# RS232_485_SDcard.net
KiCad netlist of a schematic drawn in Altium Designer
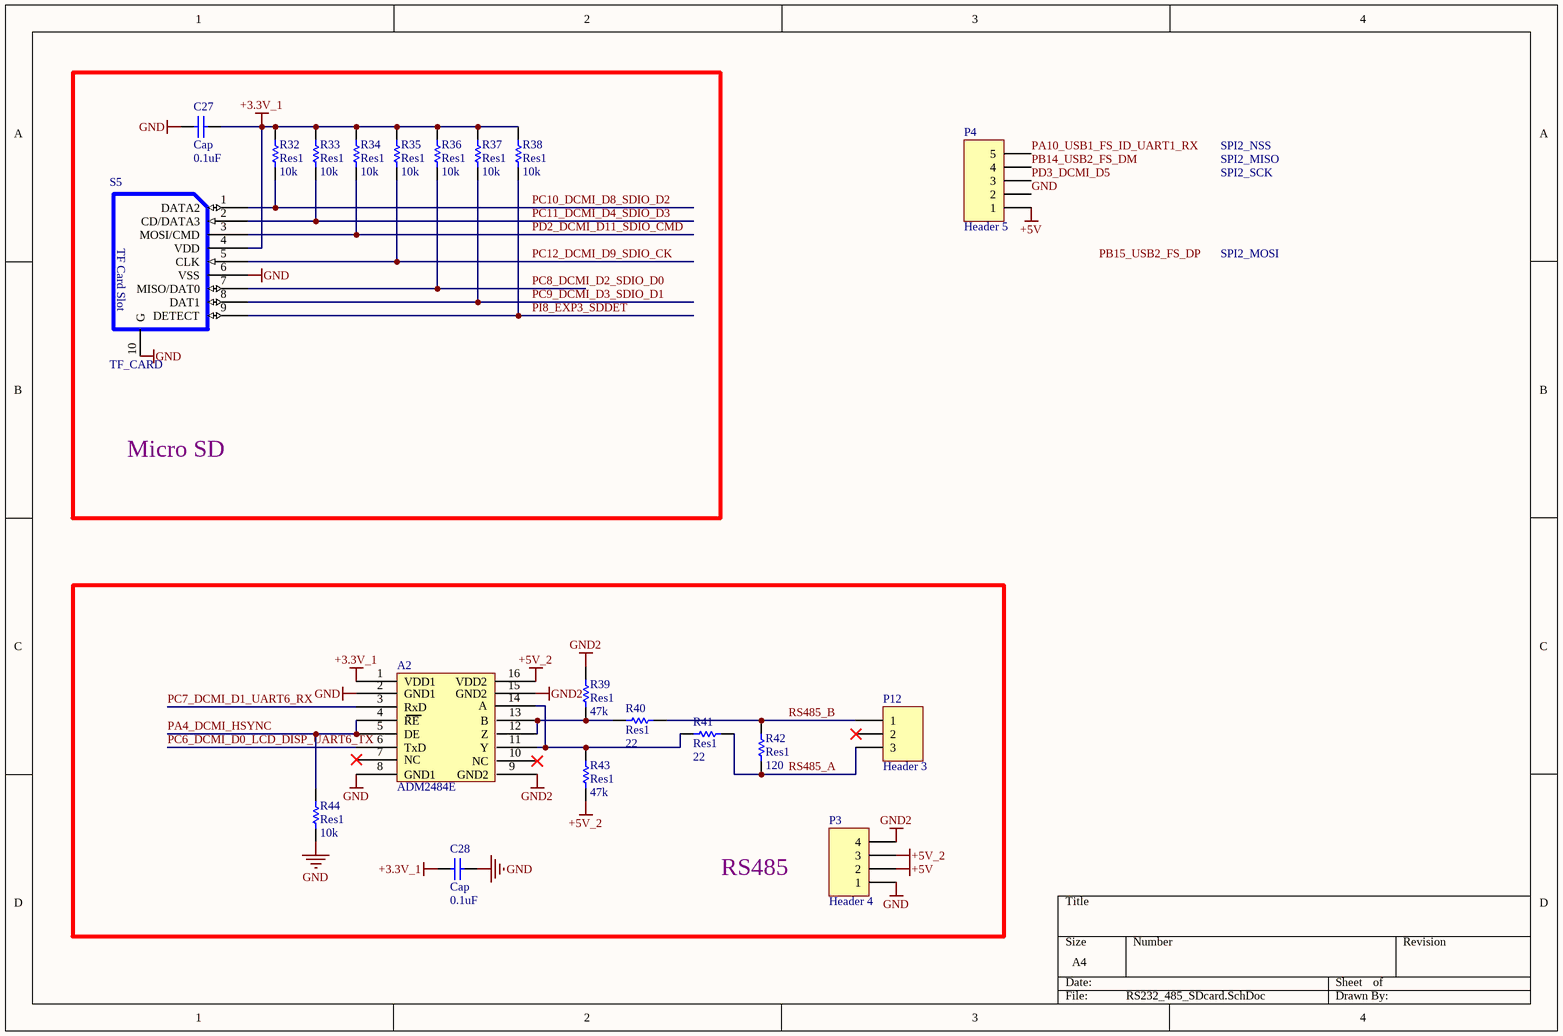
[diagram p0: RS232_485_SDcard.SchDoc]

(export (version "E")
  (design (tool "Eeschema 10.0.6"))
  (components
    (comp (ref "A2") (value "ADM2484E") (footprint "RW-16") (libsource (lib "lib-KJ") (part "ADM2484E")))
    (comp (ref "C27")
      (value "Cap")
      (footprint "0805_C")
      (description "Capacitor")
      (fields (field (name "ALTIUM_VALUE") "0.1uF") (field (name "PUBLISHER") "Altium Limited"))
      (libsource (lib "Miscellaneous Devices") (part "Cap"))
    )
    (comp (ref "C28")
      (value "Cap")
      (footprint "0805_C")
      (description "Capacitor")
      (fields (field (name "ALTIUM_VALUE") "0.1uF") (field (name "PUBLISHER") "Altium Limited"))
      (libsource (lib "Miscellaneous Devices") (part "Cap"))
    )
    (comp (ref "P3")
      (value "Header 4")
      (footprint "B0505S-1W")
      (description "Header, 4-Pin")
      (fields (field (name "PUBLISHER") "Altium Limited"))
      (libsource (lib "Miscellaneous Connectors") (part "Header 4"))
    )
    (comp (ref "P4")
      (value "Header 5")
      (footprint "DIN 固定座 方型 5P TO PCB 2003")
      (description "Header, 5-Pin")
      (fields (field (name "PUBLISHER") "Altium Limited"))
      (libsource (lib "Miscellaneous Connectors") (part "Header 5"))
    )
    (comp (ref "P12")
      (value "Header 3")
      (footprint "歐式端子*3p")
      (description "Header, 3-Pin")
      (fields (field (name "PUBLISHER") "Altium Limited"))
      (libsource (lib "Miscellaneous Connectors") (part "Header 3"))
    )
    (comp (ref "R32")
      (value "Res1")
      (footprint "0805_C")
      (description "Resistor")
      (fields (field (name "ALTIUM_VALUE") "10k") (field (name "PUBLISHER") "Altium Limited"))
      (libsource (lib "Miscellaneous Devices") (part "Res1"))
    )
    (comp (ref "R33")
      (value "Res1")
      (footprint "0805_C")
      (description "Resistor")
      (fields (field (name "ALTIUM_VALUE") "10k") (field (name "PUBLISHER") "Altium Limited"))
      (libsource (lib "Miscellaneous Devices") (part "Res1"))
    )
    (comp (ref "R34")
      (value "Res1")
      (footprint "0805_C")
      (description "Resistor")
      (fields (field (name "ALTIUM_VALUE") "10k") (field (name "PUBLISHER") "Altium Limited"))
      (libsource (lib "Miscellaneous Devices") (part "Res1"))
    )
    (comp (ref "R35")
      (value "Res1")
      (footprint "0805_C")
      (description "Resistor")
      (fields (field (name "ALTIUM_VALUE") "10k") (field (name "PUBLISHER") "Altium Limited"))
      (libsource (lib "Miscellaneous Devices") (part "Res1"))
    )
    (comp (ref "R36")
      (value "Res1")
      (footprint "0805_C")
      (description "Resistor")
      (fields (field (name "ALTIUM_VALUE") "10k") (field (name "PUBLISHER") "Altium Limited"))
      (libsource (lib "Miscellaneous Devices") (part "Res1"))
    )
    (comp (ref "R37")
      (value "Res1")
      (footprint "0805_C")
      (description "Resistor")
      (fields (field (name "ALTIUM_VALUE") "10k") (field (name "PUBLISHER") "Altium Limited"))
      (libsource (lib "Miscellaneous Devices") (part "Res1"))
    )
    (comp (ref "R38")
      (value "Res1")
      (footprint "0805_C")
      (description "Resistor")
      (fields (field (name "ALTIUM_VALUE") "10k") (field (name "PUBLISHER") "Altium Limited"))
      (libsource (lib "Miscellaneous Devices") (part "Res1"))
    )
    (comp (ref "R39")
      (value "Res1")
      (footprint "0805_C")
      (description "Resistor")
      (fields (field (name "ALTIUM_VALUE") "47k") (field (name "PUBLISHER") "Altium Limited"))
      (libsource (lib "Miscellaneous Devices") (part "Res1"))
    )
    (comp (ref "R40")
      (value "Res1")
      (footprint "0805_C")
      (description "Resistor")
      (fields (field (name "ALTIUM_VALUE") "22") (field (name "PUBLISHER") "Altium Limited"))
      (libsource (lib "Miscellaneous Devices") (part "Res1"))
    )
    (comp (ref "R41")
      (value "Res1")
      (footprint "0805_C")
      (description "Resistor")
      (fields (field (name "ALTIUM_VALUE") "22") (field (name "PUBLISHER") "Altium Limited"))
      (libsource (lib "Miscellaneous Devices") (part "Res1"))
    )
    (comp (ref "R42")
      (value "Res1")
      (footprint "0805_C")
      (description "Resistor")
      (fields (field (name "ALTIUM_VALUE") "120") (field (name "PUBLISHER") "Altium Limited"))
      (libsource (lib "Miscellaneous Devices") (part "Res1"))
    )
    (comp (ref "R43")
      (value "Res1")
      (footprint "0805_C")
      (description "Resistor")
      (fields (field (name "ALTIUM_VALUE") "47k") (field (name "PUBLISHER") "Altium Limited"))
      (libsource (lib "Miscellaneous Devices") (part "Res1"))
    )
    (comp (ref "R44")
      (value "Res1")
      (footprint "0805_C")
      (description "Resistor")
      (fields (field (name "ALTIUM_VALUE") "10k") (field (name "PUBLISHER") "Altium Limited"))
      (libsource (lib "Miscellaneous Devices") (part "Res1"))
    )
    (comp (ref "S5")
      (value "TF_CARD")
      (footprint "TF-CARD")
      (libsource (lib "STM32F4x9IG-Mother-B-SCH") (part "TF_CARD"))
    )
  )
  (nets
    (net (code "1") (name "+3.3V_1") (class "Default")
      (node (ref "A2") (pin "1") (pinfunction "VDD1_1") (pintype "passive"))
      (node (ref "C27") (pin "1") (pinfunction "1_1") (pintype "passive"))
      (node (ref "C28") (pin "1") (pinfunction "1_1") (pintype "passive"))
      (node (ref "R32") (pin "1") (pinfunction "1_1") (pintype "passive"))
      (node (ref "R33") (pin "1") (pinfunction "1_1") (pintype "passive"))
      (node (ref "R34") (pin "1") (pinfunction "1_1") (pintype "passive"))
      (node (ref "R35") (pin "1") (pinfunction "1_1") (pintype "passive"))
      (node (ref "R36") (pin "1") (pinfunction "1_1") (pintype "passive"))
      (node (ref "R37") (pin "1") (pinfunction "1_1") (pintype "passive"))
      (node (ref "R38") (pin "1") (pinfunction "1_1") (pintype "passive"))
      (node (ref "S5") (pin "4") (pinfunction "VDD_4") (pintype "power_in"))
    )
    (net (code "2") (name "+5V") (class "Default")
      (node (ref "P3") (pin "2") (pinfunction "2_2") (pintype "passive"))
      (node (ref "P4") (pin "1") (pinfunction "1_1") (pintype "passive"))
    )
    (net (code "3") (name "+5V_2") (class "Default")
      (node (ref "A2") (pin "16") (pinfunction "VDD2_16") (pintype "passive"))
      (node (ref "P3") (pin "3") (pinfunction "3_3") (pintype "passive"))
      (node (ref "R43") (pin "2") (pinfunction "2_2") (pintype "passive"))
    )
    (net (code "4") (name "/PA4_DCMI_HSYNC") (class "Default")
      (node (ref "A2") (pin "4") (pinfunction "RE_4") (pintype "passive"))
      (node (ref "A2") (pin "5") (pinfunction "DE_5") (pintype "passive"))
      (node (ref "R44") (pin "2") (pinfunction "2_2") (pintype "passive"))
    )
    (net (code "5") (name "/PA10_USB1_FS_ID_UART1_RX") (class "Default")
      (node (ref "P4") (pin "5") (pinfunction "5_5") (pintype "passive"))
    )
    (net (code "6") (name "/PB14_USB2_FS_DM") (class "Default")
      (node (ref "P4") (pin "4") (pinfunction "4_4") (pintype "passive"))
    )
    (net (code "8") (name "/PC6_DCMI_D0_LCD_DISP_UART6_TX") (class "Default")
      (node (ref "A2") (pin "6") (pinfunction "TxD_6") (pintype "passive"))
    )
    (net (code "9") (name "/PC7_DCMI_D1_UART6_RX") (class "Default")
      (node (ref "A2") (pin "3") (pinfunction "RxD_3") (pintype "passive"))
    )
    (net (code "10") (name "/PC8_DCMI_D2_SDIO_D0") (class "Default")
      (node (ref "R36") (pin "2") (pinfunction "2_2") (pintype "passive"))
      (node (ref "S5") (pin "7") (pinfunction "MISO/DAT0_7") (pintype "bidirectional"))
    )
    (net (code "11") (name "/PC9_DCMI_D3_SDIO_D1") (class "Default")
      (node (ref "R37") (pin "2") (pinfunction "2_2") (pintype "passive"))
      (node (ref "S5") (pin "8") (pinfunction "DAT1_8") (pintype "bidirectional"))
    )
    (net (code "12") (name "/PC10_DCMI_D8_SDIO_D2") (class "Default")
      (node (ref "R32") (pin "2") (pinfunction "2_2") (pintype "passive"))
      (node (ref "S5") (pin "1") (pinfunction "DATA2_1") (pintype "bidirectional"))
    )
    (net (code "13") (name "/PC11_DCMI_D4_SDIO_D3") (class "Default")
      (node (ref "R33") (pin "2") (pinfunction "2_2") (pintype "passive"))
      (node (ref "S5") (pin "2") (pinfunction "CD/DATA3_2") (pintype "input"))
    )
    (net (code "14") (name "/PC12_DCMI_D9_SDIO_CK") (class "Default")
      (node (ref "R35") (pin "2") (pinfunction "2_2") (pintype "passive"))
      (node (ref "S5") (pin "5") (pinfunction "CLK_5") (pintype "input"))
    )
    (net (code "15") (name "/PD2_DCMI_D11_SDIO_CMD") (class "Default")
      (node (ref "R34") (pin "2") (pinfunction "2_2") (pintype "passive"))
      (node (ref "S5") (pin "3") (pinfunction "MOSI/CMD_3") (pintype "passive"))
    )
    (net (code "16") (name "/PD3_DCMI_D5") (class "Default")
      (node (ref "P4") (pin "3") (pinfunction "3_3") (pintype "passive"))
    )
    (net (code "17") (name "/PI8_EXP3_SDDET") (class "Default")
      (node (ref "R38") (pin "2") (pinfunction "2_2") (pintype "passive"))
      (node (ref "S5") (pin "9") (pinfunction "DETECT_9") (pintype "bidirectional"))
    )
    (net (code "18") (name "/RS485_A") (class "Default")
      (node (ref "P12") (pin "3") (pinfunction "3_3") (pintype "passive"))
      (node (ref "R41") (pin "1") (pinfunction "1_1") (pintype "passive"))
      (node (ref "R42") (pin "2") (pinfunction "2_2") (pintype "passive"))
    )
    (net (code "19") (name "/RS485_B") (class "Default")
      (node (ref "P12") (pin "1") (pinfunction "1_1") (pintype "passive"))
      (node (ref "R40") (pin "1") (pinfunction "1_1") (pintype "passive"))
      (node (ref "R42") (pin "1") (pinfunction "1_1") (pintype "passive"))
    )
    (net (code "20") (name "GND") (class "Default")
      (node (ref "A2") (pin "2") (pinfunction "GND1_2") (pintype "passive"))
      (node (ref "A2") (pin "8") (pinfunction "GND1_8") (pintype "passive"))
      (node (ref "C27") (pin "2") (pinfunction "2_2") (pintype "passive"))
      (node (ref "C28") (pin "2") (pinfunction "2_2") (pintype "passive"))
      (node (ref "P3") (pin "1") (pinfunction "1_1") (pintype "passive"))
      (node (ref "P4") (pin "2") (pinfunction "2_2") (pintype "passive"))
      (node (ref "R44") (pin "1") (pinfunction "1_1") (pintype "passive"))
      (node (ref "S5") (pin "10") (pinfunction "G_10") (pintype "passive"))
      (node (ref "S5") (pin "6") (pinfunction "VSS_6") (pintype "power_in"))
    )
    (net (code "21") (name "GND2") (class "Default")
      (node (ref "A2") (pin "15") (pinfunction "GND2_15") (pintype "passive"))
      (node (ref "A2") (pin "9") (pinfunction "GND2_9") (pintype "passive"))
      (node (ref "P3") (pin "4") (pinfunction "4_4") (pintype "passive"))
      (node (ref "R39") (pin "1") (pinfunction "1_1") (pintype "passive"))
    )
    (net (code "22") (name "Net-(A2-A)") (class "Default")
      (node (ref "A2") (pin "11") (pinfunction "Y_11") (pintype "passive"))
      (node (ref "A2") (pin "14") (pinfunction "A_14") (pintype "passive"))
      (node (ref "R41") (pin "2") (pinfunction "2_2") (pintype "passive"))
      (node (ref "R43") (pin "1") (pinfunction "1_1") (pintype "passive"))
    )
    (net (code "23") (name "Net-(A2-B)") (class "Default")
      (node (ref "A2") (pin "12") (pinfunction "Z_12") (pintype "passive"))
      (node (ref "A2") (pin "13") (pinfunction "B_13") (pintype "passive"))
      (node (ref "R39") (pin "2") (pinfunction "2_2") (pintype "passive"))
      (node (ref "R40") (pin "2") (pinfunction "2_2") (pintype "passive"))
    )
    (net (code "24") (name "unconnected-(A2-NC-Pad7)") (class "Default")
      (node (ref "A2") (pin "7") (pinfunction "NC_7") (pintype "passive+no_connect"))
    )
    (net (code "25") (name "unconnected-(A2-NC-Pad10)") (class "Default")
      (node (ref "A2") (pin "10") (pinfunction "NC_10") (pintype "passive+no_connect"))
    )
    (net (code "26") (name "unconnected-(P12-Pad2)") (class "Default")
      (node (ref "P12") (pin "2") (pinfunction "2_2") (pintype "passive+no_connect"))
    )
  )
)
